# SWM050_TSOP8.net
KiCad netlist of a schematic drawn in EAGLE
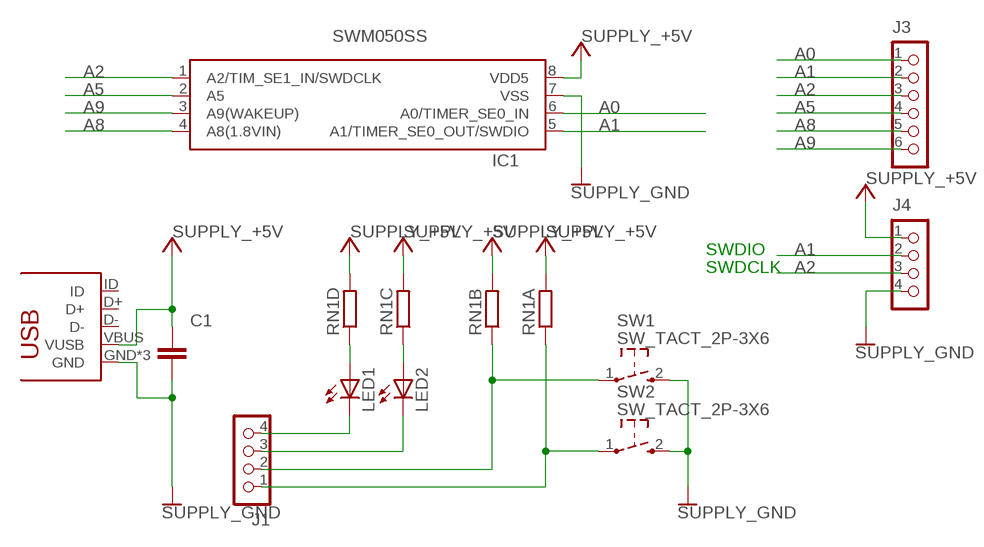
[diagram p0: schematic, sheet 1]

(export (version "E")
  (design (tool "Eeschema 10.0.6"))
  (components
    (comp (ref "C1")
      (value "CAPACITOR_NPOL-0603")
      (footprint "eagle-import:C603")
      (libsource (lib "eagle-import") (part "CAPACITOR_NPOL-0603"))
    )
    (comp (ref "IC1")
      (value "SWM050I2P7\"\"")
      (footprint "eagle-import:TSOP8_065")
      (libsource (lib "eagle-import") (part "SWM050I2P7{dblquote}{dblquote}"))
    )
    (comp (ref "J1")
      (value "CON_HEADER_1X04")
      (footprint "eagle-import:M1X4")
      (libsource (lib "eagle-import") (part "CON_HEADER_1X04"))
    )
    (comp (ref "J3")
      (value "CON_HEADER_1X06-PTH")
      (footprint "eagle-import:M1X6")
      (libsource (lib "eagle-import") (part "CON_HEADER_1X06-PTH"))
    )
    (comp (ref "J4")
      (value "CON_HEADER_1X04")
      (footprint "eagle-import:M1X4")
      (libsource (lib "eagle-import") (part "CON_HEADER_1X04"))
    )
    (comp (ref "LED1")
      (value "LED-0603")
      (footprint "eagle-import:LED-603")
      (libsource (lib "eagle-import") (part "LED-0603"))
    )
    (comp (ref "LED2")
      (value "LED-0603")
      (footprint "eagle-import:LED-603")
      (libsource (lib "eagle-import") (part "LED-0603"))
    )
    (comp (ref "RN1")
      (value "RESISTOR_ARRAY_4")
      (footprint "eagle-import:RN8P-4R-CRA06S")
      (libsource (lib "eagle-import") (part "RESISTOR_ARRAY_4"))
    )
    (comp (ref "SW1")
      (value "SW_TACT_2P-3X6")
      (footprint "eagle-import:SW_TACT_3X6")
      (libsource (lib "eagle-import") (part "SW_TACT_2P-3X6"))
    )
    (comp (ref "SW2")
      (value "SW_TACT_2P-3X6")
      (footprint "eagle-import:SW_TACT_3X6")
      (libsource (lib "eagle-import") (part "SW_TACT_2P-3X6"))
    )
    (comp (ref "U$1")
      (value "CON_USB_MICRO_SMD")
      (footprint "eagle-import:MICRO_USB_SMD")
      (libsource (lib "eagle-import") (part "CON_USB_MICRO_SMD"))
    )
  )
  (nets
    (net (code "1") (name "/A0") (class "Default")
      (node (ref "IC1") (pin "6") (pinfunction "A0/TIMER_SE0_IN_6") (pintype "bidirectional"))
      (node (ref "J3") (pin "1") (pinfunction "1_1") (pintype "bidirectional"))
    )
    (net (code "2") (name "/A1") (class "Default")
      (node (ref "IC1") (pin "5") (pinfunction "A1/TIMER_SE0_OUT/SWDIO_5") (pintype "bidirectional"))
      (node (ref "J3") (pin "2") (pinfunction "2_2") (pintype "bidirectional"))
      (node (ref "J4") (pin "2") (pinfunction "2_2") (pintype "bidirectional"))
    )
    (net (code "3") (name "/A2") (class "Default")
      (node (ref "IC1") (pin "1") (pinfunction "A2/TIM_SE1_IN/SWDCLK_1") (pintype "bidirectional"))
      (node (ref "J3") (pin "3") (pinfunction "3_3") (pintype "passive"))
      (node (ref "J4") (pin "3") (pinfunction "3_3") (pintype "bidirectional"))
    )
    (net (code "4") (name "/A5") (class "Default")
      (node (ref "IC1") (pin "2") (pinfunction "A5_2") (pintype "bidirectional"))
      (node (ref "J3") (pin "4") (pinfunction "4_4") (pintype "passive"))
    )
    (net (code "5") (name "/A8") (class "Default")
      (node (ref "IC1") (pin "4") (pinfunction "A8(1.8VIN)_4") (pintype "bidirectional"))
      (node (ref "J3") (pin "5") (pinfunction "5_5") (pintype "passive"))
    )
    (net (code "6") (name "/A9") (class "Default")
      (node (ref "IC1") (pin "3") (pinfunction "A9(WAKEUP)_3") (pintype "bidirectional"))
      (node (ref "J3") (pin "6") (pinfunction "6_6") (pintype "passive"))
    )
    (net (code "7") (name "Net-(J1-Pad1)") (class "Default")
      (node (ref "J1") (pin "1") (pinfunction "1_1") (pintype "bidirectional"))
      (node (ref "RN1") (pin "1") (pinfunction "1_1") (pintype "passive"))
      (node (ref "SW2") (pin "1") (pinfunction "1_1") (pintype "passive"))
    )
    (net (code "8") (name "Net-(J1-Pad3)") (class "Default")
      (node (ref "J1") (pin "3") (pinfunction "3_3") (pintype "bidirectional"))
      (node (ref "LED2") (pin "C") (pinfunction "C_C") (pintype "passive"))
    )
    (net (code "9") (name "Net-(J1-Pad4)") (class "Default")
      (node (ref "J1") (pin "4") (pinfunction "4_4") (pintype "bidirectional"))
      (node (ref "LED1") (pin "C") (pinfunction "C_C") (pintype "passive"))
    )
    (net (code "10") (name "Net-(RN1B-1)") (class "Default")
      (node (ref "J1") (pin "2") (pinfunction "2_2") (pintype "bidirectional"))
      (node (ref "RN1") (pin "2") (pinfunction "1_2") (pintype "passive"))
      (node (ref "SW1") (pin "1") (pinfunction "1_1") (pintype "passive"))
    )
    (net (code "11") (name "Net-(RN1C-1)") (class "Default")
      (node (ref "LED2") (pin "A") (pinfunction "A_A") (pintype "passive"))
      (node (ref "RN1") (pin "3") (pinfunction "1_3") (pintype "passive"))
    )
    (net (code "12") (name "Net-(RN1D-1)") (class "Default")
      (node (ref "LED1") (pin "A") (pinfunction "A_A") (pintype "passive"))
      (node (ref "RN1") (pin "4") (pinfunction "1_4") (pintype "passive"))
    )
    (net (code "13") (name "SUPPLY_+5V") (class "Default")
      (node (ref "C1") (pin "1") (pinfunction "1_1") (pintype "passive"))
      (node (ref "IC1") (pin "8") (pinfunction "VDD5_8") (pintype "bidirectional"))
      (node (ref "J4") (pin "1") (pinfunction "1_1") (pintype "bidirectional"))
      (node (ref "RN1") (pin "5") (pinfunction "2_5") (pintype "passive"))
      (node (ref "RN1") (pin "6") (pinfunction "2_6") (pintype "passive"))
      (node (ref "RN1") (pin "7") (pinfunction "2_7") (pintype "passive"))
      (node (ref "RN1") (pin "8") (pinfunction "2_8") (pintype "passive"))
      (node (ref "U$1") (pin "VBUS") (pinfunction "VUSB_VBUS") (pintype "bidirectional"))
    )
    (net (code "14") (name "SUPPLY_GND") (class "Default")
      (node (ref "C1") (pin "2") (pinfunction "2_2") (pintype "passive"))
      (node (ref "IC1") (pin "7") (pinfunction "VSS_7") (pintype "bidirectional"))
      (node (ref "J4") (pin "4") (pinfunction "4_4") (pintype "bidirectional"))
      (node (ref "SW1") (pin "2") (pinfunction "3_2") (pintype "passive"))
      (node (ref "SW2") (pin "2") (pinfunction "3_2") (pintype "passive"))
      (node (ref "U$1") (pin "GND") (pinfunction "GND_GND") (pintype "bidirectional"))
      (node (ref "U$1") (pin "P$2") (pinfunction "GND_P$2") (pintype "bidirectional"))
      (node (ref "U$1") (pin "P$3") (pinfunction "GND_P$3") (pintype "bidirectional"))
    )
    (net (code "15") (name "unconnected-(U$1-PadD+)") (class "Default")
      (node (ref "U$1") (pin "D+") (pinfunction "D+_D+") (pintype "bidirectional"))
    )
    (net (code "16") (name "unconnected-(U$1-PadD-)") (class "Default")
      (node (ref "U$1") (pin "D-") (pinfunction "D-_D-") (pintype "bidirectional"))
    )
    (net (code "17") (name "unconnected-(U$1-PadID)") (class "Default")
      (node (ref "U$1") (pin "ID") (pinfunction "ID_ID") (pintype "bidirectional"))
    )
  )
)
